# Mouse-Wheel-v2-SCH.net
KiCad netlist of a schematic drawn in Altium Designer
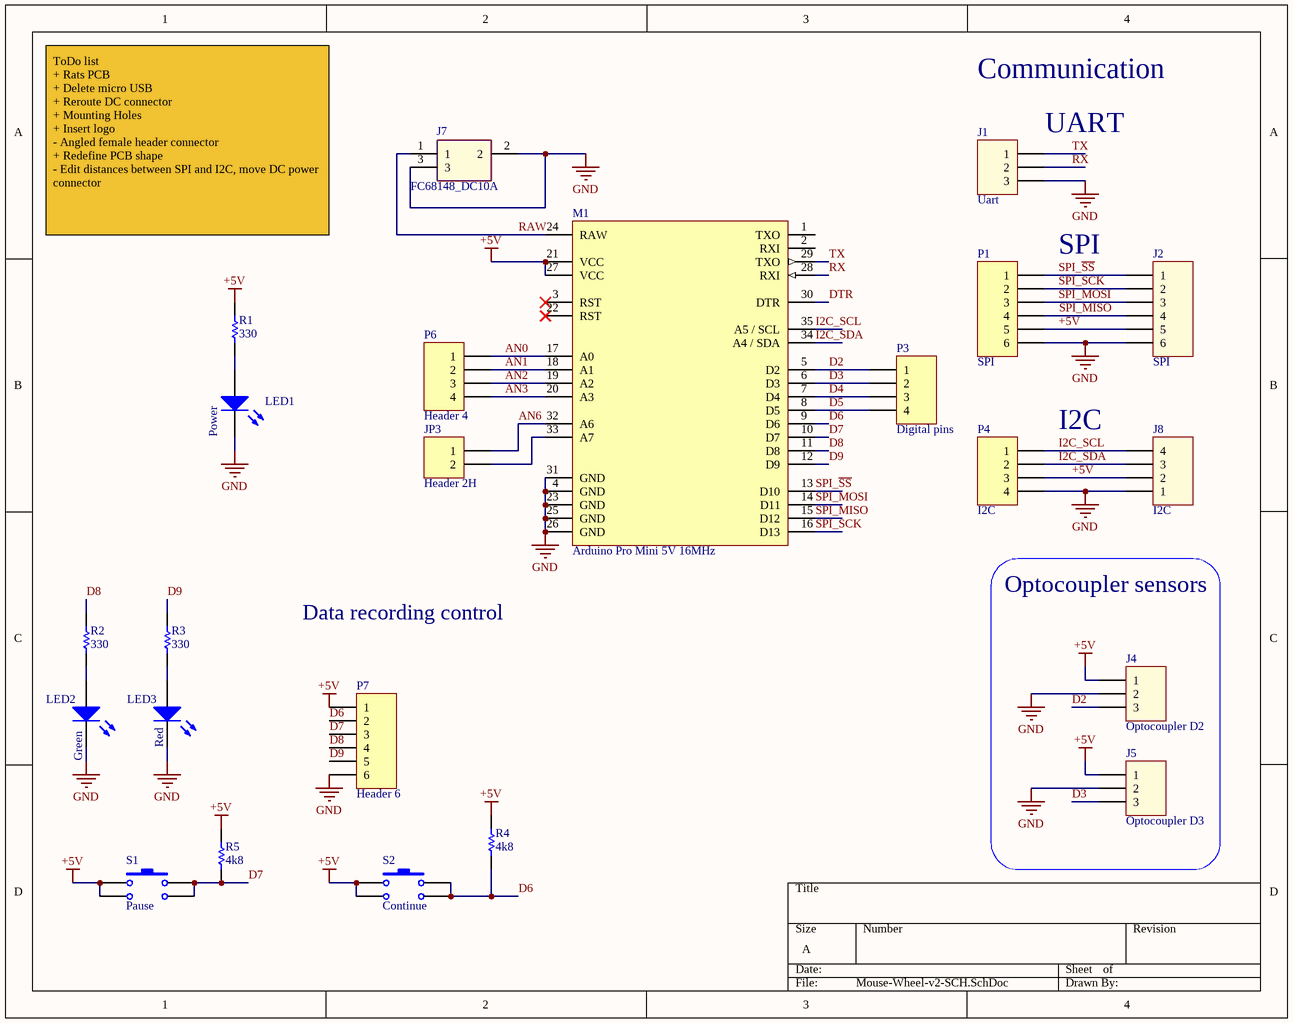
[diagram p0: Mouse-Wheel-v2-SCH.SchDoc]

(export (version "E")
  (design (tool "Eeschema 10.0.6"))
  (components
    (comp (ref "J1")
      (value "Uart")
      (footprint "61900311121")
      (description "WR-WTB 2.54mm Male Locking Header, 3p")
      (fields (field (name "PART NUMBER") "61900311121") (field (name "PUBLISHER") "Wurth Elektronik"))
      (libsource (lib "") (part "61900311121_1"))
    )
    (comp (ref "J2")
      (value "SPI")
      (footprint "61900611021")
      (description "WR-WTB 2.54mm Male Left Angled Header Bottom Locking, 6p")
      (fields (field (name "PART NUMBER") "61900611021") (field (name "PUBLISHER") "Wurth Elektronik"))
      (libsource (lib "ALTIUM-WTB_2_54_MALE_RIGHT_ANGLED_TOP_LOCKING_6190XX19521") (part "61900611021"))
    )
    (comp (ref "J4")
      (value "Optocoupler D2")
      (footprint "61900311121")
      (description "WR-WTB 2.54mm Male Locking Header, 3p")
      (fields (field (name "PART NUMBER") "61900311121") (field (name "PUBLISHER") "Wurth Elektronik"))
      (libsource (lib "ALTIUM-WTB_2_54_MALE_RIGHT_ANGLED_TOP_LOCKING_6190XX19521") (part "61900311121"))
    )
    (comp (ref "J5")
      (value "Optocoupler D3")
      (footprint "61900311121")
      (description "WR-WTB 2.54mm Male Locking Header, 3p")
      (fields (field (name "PART NUMBER") "61900311121") (field (name "PUBLISHER") "Wurth Elektronik"))
      (libsource (lib "ALTIUM-WTB_2_54_MALE_RIGHT_ANGLED_TOP_LOCKING_6190XX19521") (part "61900311121"))
    )
    (comp (ref "J7")
      (value "FC68148_DC10A")
      (footprint "FC68148DC10A")
      (description "CLIFF ELECTRONIC COMPONENTS - FC68148 DC10A - SOCKET, PCB, DC POWER, 2.1MM, PK10")
      (fields (field (name "MANUFACTURER_PART_NUMBER") "FC68148 DC10A"))
      (libsource (lib "FC68148_DC10A") (part "FC68148_DC10A"))
    )
    (comp (ref "J8")
      (value "I2C")
      (footprint "61900411021")
      (description "WR-WTB 2.54mm Male Left Angled Header Bottom Locking, 4p")
      (fields (field (name "PART NUMBER") "61900411021") (field (name "PUBLISHER") "Wurth Elektronik"))
      (libsource (lib "ALTIUM-WTB_2_54_MALE_RIGHT_ANGLED_TOP_LOCKING_6190XX19521") (part "61900411021"))
    )
    (comp (ref "JP3")
      (value "Header 2H")
      (footprint "HDR1X2")
      (description "Header, 2-Pin, Right Angle")
      (fields (field (name "PUBLISHER") "Altium Limited"))
      (libsource (lib "KNoT_Thing") (part "Header 2H"))
    )
    (comp (ref "LED1")
      (value "Power")
      (footprint "LED")
      (description "Typical RED, GREEN, YELLOW, AMBER GaAs LED")
      (fields (field (name "PUBLISHER") "Altium Limited"))
      (libsource (lib "KNoT_Thing") (part "LED"))
    )
    (comp (ref "LED2")
      (value "Green")
      (footprint "LED RADIAL 5MM GREEN")
      (description "LED RADIAL")
      (libsource (lib "KNoT-Gateway Library") (part "LED RADIAL 5MM GREEN"))
    )
    (comp (ref "LED3")
      (value "Red")
      (footprint "LED RADIAL 5MM RED")
      (description "LED RADIAL")
      (libsource (lib "KNoT-Gateway Library") (part "LED RADIAL 5MM RED"))
    )
    (comp (ref "M1")
      (value "Arduino Pro Mini 5V 16MHz")
      (footprint "Arduino Pro Mini")
      (libsource (lib "KNoT_Thing") (part "Arduino Pro Mini 5V 16MHz"))
    )
    (comp (ref "P1")
      (value "SPI")
      (footprint "HDR1X6")
      (description "Header, 6-Pin")
      (fields (field (name "PUBLISHER") "Altium Limited"))
      (libsource (lib "KNoT_Thing") (part "Header 6"))
    )
    (comp (ref "P3")
      (value "Digital pins")
      (footprint "HDR1X4")
      (description "Header, 4-Pin")
      (fields (field (name "PUBLISHER") "Altium Limited"))
      (libsource (lib "") (part "Header 4_1"))
    )
    (comp (ref "P4")
      (value "I2C")
      (footprint "HDR1X4")
      (description "Header, 4-Pin")
      (fields (field (name "PUBLISHER") "Altium Limited"))
      (libsource (lib "KNoT_Thing") (part "Header 4"))
    )
    (comp (ref "P6")
      (value "Header 4")
      (footprint "HDR1X4")
      (description "Header, 4-Pin")
      (fields (field (name "PUBLISHER") "Altium Limited"))
      (libsource (lib "KNoT_Thing") (part "Header 4"))
    )
    (comp (ref "P7")
      (value "Header 6")
      (footprint "HDR1X6")
      (description "Header, 6-Pin")
      (fields (field (name "PUBLISHER") "Altium Limited"))
      (libsource (lib "") (part "Header 6_1"))
    )
    (comp (ref "R1")
      (value "330")
      (footprint "AXIAL-3mm")
      (description "Resistor")
      (fields (field (name "PUBLISHER") "Altium Limited"))
      (libsource (lib "KNoT_Thing") (part "Res1"))
    )
    (comp (ref "R2")
      (value "330")
      (footprint "AXIAL-3mm")
      (description "Resistor")
      (fields (field (name "PUBLISHER") "Altium Limited"))
      (libsource (lib "KNoT_Thing") (part "Res1"))
    )
    (comp (ref "R3")
      (value "330")
      (footprint "AXIAL-3mm")
      (description "Resistor")
      (fields (field (name "PUBLISHER") "Altium Limited"))
      (libsource (lib "KNoT_Thing") (part "Res1"))
    )
    (comp (ref "R4")
      (value "4k8")
      (footprint "AXIAL-3mm")
      (description "Resistor")
      (fields (field (name "PUBLISHER") "Altium Limited"))
      (libsource (lib "KNoT_Thing") (part "Res1"))
    )
    (comp (ref "R5")
      (value "4k8")
      (footprint "AXIAL-3mm")
      (description "Resistor")
      (fields (field (name "PUBLISHER") "Altium Limited"))
      (libsource (lib "KNoT_Thing") (part "Res1"))
    )
    (comp (ref "S1")
      (value "Pause")
      (footprint "SW-TACT")
      (description "B3F-1002 SWITCH TACT 6MM MOM 150GF")
      (fields (field (name "PUBLISHER") "Altium Limited"))
      (libsource (lib "KNoT_Thing") (part "SW-PB"))
    )
    (comp (ref "S2")
      (value "Continue")
      (footprint "SW-TACT")
      (description "B3F-1002 SWITCH TACT 6MM MOM 150GF")
      (fields (field (name "PUBLISHER") "Altium Limited"))
      (libsource (lib "KNoT_Thing") (part "SW-PB"))
    )
  )
  (nets
    (net (code "1") (name "+5V") (class "Default")
      (node (ref "J2") (pin "5") (pinfunction "5_5") (pintype "passive"))
      (node (ref "J4") (pin "1") (pinfunction "1_1") (pintype "passive"))
      (node (ref "J5") (pin "1") (pinfunction "1_1") (pintype "passive"))
      (node (ref "J8") (pin "2") (pinfunction "2_2") (pintype "passive"))
      (node (ref "M1") (pin "21") (pinfunction "VCC_21") (pintype "passive"))
      (node (ref "M1") (pin "27") (pinfunction "VCC_27") (pintype "passive"))
      (node (ref "P1") (pin "5") (pinfunction "5_5") (pintype "passive"))
      (node (ref "P4") (pin "3") (pinfunction "3_3") (pintype "passive"))
      (node (ref "P7") (pin "1") (pinfunction "1_1") (pintype "passive"))
      (node (ref "R1") (pin "1") (pinfunction "1_1") (pintype "passive"))
      (node (ref "R4") (pin "2") (pinfunction "2_2") (pintype "passive"))
      (node (ref "R5") (pin "2") (pinfunction "2_2") (pintype "passive"))
      (node (ref "S1") (pin "1") (pinfunction "1_1") (pintype "passive"))
      (node (ref "S1") (pin "2") (pinfunction "2_2") (pintype "passive"))
      (node (ref "S2") (pin "1") (pinfunction "1_1") (pintype "passive"))
      (node (ref "S2") (pin "2") (pinfunction "2_2") (pintype "passive"))
    )
    (net (code "2") (name "/AN0") (class "Default")
      (node (ref "M1") (pin "17") (pinfunction "A0_17") (pintype "passive"))
      (node (ref "P6") (pin "1") (pinfunction "1_1") (pintype "passive"))
    )
    (net (code "3") (name "/AN1") (class "Default")
      (node (ref "M1") (pin "18") (pinfunction "A1_18") (pintype "passive"))
      (node (ref "P6") (pin "2") (pinfunction "2_2") (pintype "passive"))
    )
    (net (code "4") (name "/AN2") (class "Default")
      (node (ref "M1") (pin "19") (pinfunction "A2_19") (pintype "passive"))
      (node (ref "P6") (pin "3") (pinfunction "3_3") (pintype "passive"))
    )
    (net (code "5") (name "/AN3") (class "Default")
      (node (ref "M1") (pin "20") (pinfunction "A3_20") (pintype "passive"))
      (node (ref "P6") (pin "4") (pinfunction "4_4") (pintype "passive"))
    )
    (net (code "6") (name "/AN6") (class "Default")
      (node (ref "JP3") (pin "1") (pinfunction "1_1") (pintype "passive"))
      (node (ref "M1") (pin "32") (pinfunction "A6_32") (pintype "passive"))
    )
    (net (code "7") (name "/D2") (class "Default")
      (node (ref "J4") (pin "3") (pinfunction "3_3") (pintype "passive"))
      (node (ref "M1") (pin "5") (pinfunction "D2_5") (pintype "passive"))
      (node (ref "P3") (pin "1") (pinfunction "1_1") (pintype "passive"))
    )
    (net (code "8") (name "/D3") (class "Default")
      (node (ref "J5") (pin "3") (pinfunction "3_3") (pintype "passive"))
      (node (ref "M1") (pin "6") (pinfunction "D3_6") (pintype "passive"))
      (node (ref "P3") (pin "2") (pinfunction "2_2") (pintype "passive"))
    )
    (net (code "9") (name "/D4") (class "Default")
      (node (ref "M1") (pin "7") (pinfunction "D4_7") (pintype "passive"))
      (node (ref "P3") (pin "3") (pinfunction "3_3") (pintype "passive"))
    )
    (net (code "10") (name "/D5") (class "Default")
      (node (ref "M1") (pin "8") (pinfunction "D5_8") (pintype "passive"))
      (node (ref "P3") (pin "4") (pinfunction "4_4") (pintype "passive"))
    )
    (net (code "11") (name "/D6") (class "Default")
      (node (ref "M1") (pin "9") (pinfunction "D6_9") (pintype "passive"))
      (node (ref "P7") (pin "2") (pinfunction "2_2") (pintype "passive"))
      (node (ref "R4") (pin "1") (pinfunction "1_1") (pintype "passive"))
      (node (ref "S2") (pin "3") (pinfunction "3_3") (pintype "passive"))
      (node (ref "S2") (pin "4") (pinfunction "4_4") (pintype "passive"))
    )
    (net (code "12") (name "/D7") (class "Default")
      (node (ref "M1") (pin "10") (pinfunction "D7_10") (pintype "passive"))
      (node (ref "P7") (pin "3") (pinfunction "3_3") (pintype "passive"))
      (node (ref "R5") (pin "1") (pinfunction "1_1") (pintype "passive"))
      (node (ref "S1") (pin "3") (pinfunction "3_3") (pintype "passive"))
      (node (ref "S1") (pin "4") (pinfunction "4_4") (pintype "passive"))
    )
    (net (code "13") (name "/D8") (class "Default")
      (node (ref "M1") (pin "11") (pinfunction "D8_11") (pintype "passive"))
      (node (ref "P7") (pin "4") (pinfunction "4_4") (pintype "passive"))
      (node (ref "R2") (pin "1") (pinfunction "1_1") (pintype "passive"))
    )
    (net (code "14") (name "/D9") (class "Default")
      (node (ref "M1") (pin "12") (pinfunction "D9_12") (pintype "passive"))
      (node (ref "P7") (pin "5") (pinfunction "5_5") (pintype "passive"))
      (node (ref "R3") (pin "1") (pinfunction "1_1") (pintype "passive"))
    )
    (net (code "15") (name "/DTR") (class "Default")
      (node (ref "M1") (pin "30") (pinfunction "DTR_30") (pintype "passive"))
    )
    (net (code "16") (name "/I2C_SCL") (class "Default")
      (node (ref "J8") (pin "4") (pinfunction "4_4") (pintype "passive"))
      (node (ref "M1") (pin "35") (pinfunction "A5_/_SCL_35") (pintype "passive"))
      (node (ref "P4") (pin "1") (pinfunction "1_1") (pintype "passive"))
    )
    (net (code "17") (name "/I2C_SDA") (class "Default")
      (node (ref "J8") (pin "3") (pinfunction "3_3") (pintype "passive"))
      (node (ref "M1") (pin "34") (pinfunction "A4_/_SDA_34") (pintype "passive"))
      (node (ref "P4") (pin "2") (pinfunction "2_2") (pintype "passive"))
    )
    (net (code "18") (name "/RAW") (class "Default")
      (node (ref "J7") (pin "1") (pinfunction "1_1") (pintype "passive"))
      (node (ref "M1") (pin "24") (pinfunction "RAW_24") (pintype "passive"))
    )
    (net (code "19") (name "/RX") (class "Default")
      (node (ref "J1") (pin "2") (pinfunction "2_2") (pintype "passive"))
      (node (ref "M1") (pin "28") (pinfunction "RXI_28") (pintype "input"))
    )
    (net (code "20") (name "/SPI_MISO") (class "Default")
      (node (ref "J2") (pin "4") (pinfunction "4_4") (pintype "passive"))
      (node (ref "M1") (pin "15") (pinfunction "D12_15") (pintype "passive"))
      (node (ref "P1") (pin "4") (pinfunction "4_4") (pintype "passive"))
    )
    (net (code "21") (name "/SPI_MOSI") (class "Default")
      (node (ref "J2") (pin "3") (pinfunction "3_3") (pintype "passive"))
      (node (ref "M1") (pin "14") (pinfunction "D11_14") (pintype "passive"))
      (node (ref "P1") (pin "3") (pinfunction "3_3") (pintype "passive"))
    )
    (net (code "22") (name "/SPI_SCK") (class "Default")
      (node (ref "J2") (pin "2") (pinfunction "2_2") (pintype "passive"))
      (node (ref "M1") (pin "16") (pinfunction "D13_16") (pintype "passive"))
      (node (ref "P1") (pin "2") (pinfunction "2_2") (pintype "passive"))
    )
    (net (code "23") (name "/SPI_~{SS}") (class "Default")
      (node (ref "J2") (pin "1") (pinfunction "1_1") (pintype "passive"))
      (node (ref "M1") (pin "13") (pinfunction "D10_13") (pintype "passive"))
      (node (ref "P1") (pin "1") (pinfunction "1_1") (pintype "passive"))
    )
    (net (code "24") (name "/TX") (class "Default")
      (node (ref "J1") (pin "1") (pinfunction "1_1") (pintype "passive"))
      (node (ref "M1") (pin "29") (pinfunction "TXO_29") (pintype "output"))
    )
    (net (code "25") (name "GND") (class "Default")
      (node (ref "J1") (pin "3") (pinfunction "3_3") (pintype "passive"))
      (node (ref "J2") (pin "6") (pinfunction "6_6") (pintype "passive"))
      (node (ref "J4") (pin "2") (pinfunction "2_2") (pintype "passive"))
      (node (ref "J5") (pin "2") (pinfunction "2_2") (pintype "passive"))
      (node (ref "J7") (pin "2") (pinfunction "2_2") (pintype "passive"))
      (node (ref "J7") (pin "3") (pinfunction "3_3") (pintype "passive"))
      (node (ref "J8") (pin "1") (pinfunction "1_1") (pintype "passive"))
      (node (ref "LED1") (pin "2") (pinfunction "K_2") (pintype "passive"))
      (node (ref "LED2") (pin "2") (pinfunction "K_2") (pintype "passive"))
      (node (ref "LED3") (pin "2") (pinfunction "K_2") (pintype "passive"))
      (node (ref "M1") (pin "23") (pinfunction "GND_23") (pintype "passive"))
      (node (ref "M1") (pin "25") (pinfunction "GND_25") (pintype "passive"))
      (node (ref "M1") (pin "26") (pinfunction "GND_26") (pintype "passive"))
      (node (ref "M1") (pin "31") (pinfunction "GND_31") (pintype "passive"))
      (node (ref "M1") (pin "4") (pinfunction "GND_4") (pintype "passive"))
      (node (ref "P1") (pin "6") (pinfunction "6_6") (pintype "passive"))
      (node (ref "P4") (pin "4") (pinfunction "4_4") (pintype "passive"))
      (node (ref "P7") (pin "6") (pinfunction "6_6") (pintype "passive"))
    )
    (net (code "26") (name "Net-(LED1-A)") (class "Default")
      (node (ref "LED1") (pin "1") (pinfunction "A_1") (pintype "passive"))
      (node (ref "R1") (pin "2") (pinfunction "2_2") (pintype "passive"))
    )
    (net (code "27") (name "Net-(LED2-A)") (class "Default")
      (node (ref "LED2") (pin "1") (pinfunction "A_1") (pintype "passive"))
      (node (ref "R2") (pin "2") (pinfunction "2_2") (pintype "passive"))
    )
    (net (code "28") (name "Net-(LED3-A)") (class "Default")
      (node (ref "LED3") (pin "1") (pinfunction "A_1") (pintype "passive"))
      (node (ref "R3") (pin "2") (pinfunction "2_2") (pintype "passive"))
    )
    (net (code "29") (name "Net-(M1-A7)") (class "Default")
      (node (ref "JP3") (pin "2") (pinfunction "2_2") (pintype "passive"))
      (node (ref "M1") (pin "33") (pinfunction "A7_33") (pintype "passive"))
    )
    (net (code "30") (name "unconnected-(M1-RST-Pad3)") (class "Default")
      (node (ref "M1") (pin "3") (pinfunction "RST_3") (pintype "passive+no_connect"))
    )
    (net (code "31") (name "unconnected-(M1-RST-Pad22)") (class "Default")
      (node (ref "M1") (pin "22") (pinfunction "RST_22") (pintype "passive+no_connect"))
    )
    (net (code "32") (name "unconnected-(M1-RXI-Pad2)") (class "Default")
      (node (ref "M1") (pin "2") (pinfunction "RXI_2") (pintype "passive"))
    )
    (net (code "33") (name "unconnected-(M1-TXO-Pad1)") (class "Default")
      (node (ref "M1") (pin "1") (pinfunction "TXO_1") (pintype "passive"))
    )
  )
)
